# DirSpd.net
KiCad netlist of a schematic drawn in EAGLE
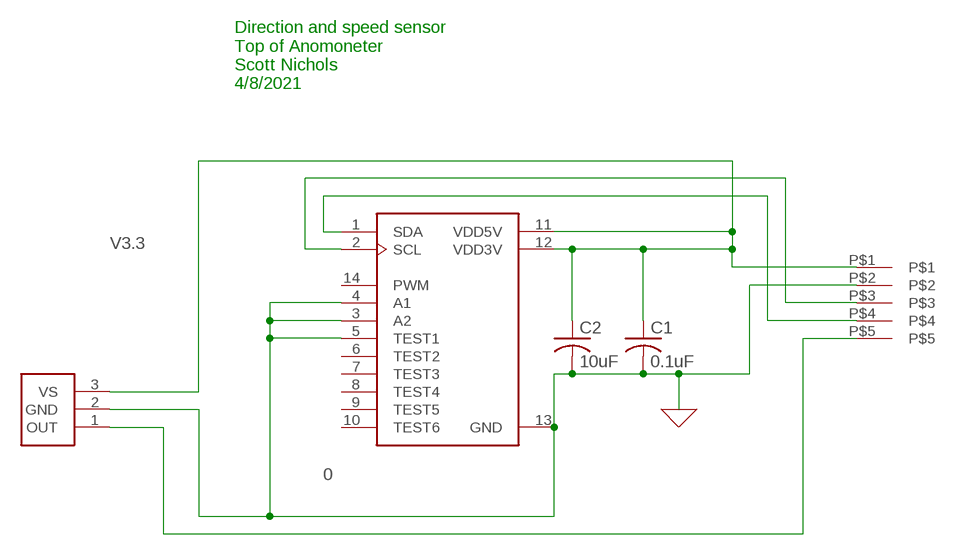
[diagram p0: schematic, sheet 1]

(export (version "E")
  (design (tool "Eeschema 10.0.6"))
  (components
    (comp (ref "C1")
      (value "0.1uF")
      (footprint "eagle-import:C0805K")
      (libsource (lib "eagle-import") (part "C-USC0805K"))
    )
    (comp (ref "C2")
      (value "10uF")
      (footprint "eagle-import:C0805K")
      (libsource (lib "eagle-import") (part "C-USC0805K"))
    )
    (comp (ref "J1")
      (value "B05B-PASK")
      (footprint "eagle-import:B05B-PASK")
      (libsource (lib "eagle-import") (part "B05B-PASK"))
    )
    (comp (ref "U1")
      (value "AS5048B")
      (footprint "eagle-import:TSSOP14")
      (libsource (lib "eagle-import") (part "AS5048B"))
    )
    (comp (ref "U2")
      (value "SS451A")
      (footprint "eagle-import:TO-92-3")
      (libsource (lib "eagle-import") (part "HONEYWELLSS451A"))
    )
  )
  (nets
    (net (code "1") (name "/V3.3") (class "Default")
      (node (ref "C1") (pin "1") (pinfunction "1_1") (pintype "passive"))
      (node (ref "C2") (pin "1") (pinfunction "1_1") (pintype "passive"))
      (node (ref "J1") (pin "P$1") (pinfunction "P$1_P$1") (pintype "bidirectional"))
      (node (ref "U1") (pin "11") (pinfunction "VDD5V_11") (pintype "bidirectional"))
      (node (ref "U1") (pin "12") (pinfunction "VDD3V_12") (pintype "bidirectional"))
      (node (ref "U2") (pin "3") (pinfunction "VS_3") (pintype "power_in"))
    )
    (net (code "2") (name "GND") (class "Default")
      (node (ref "C1") (pin "2") (pinfunction "2_2") (pintype "passive"))
      (node (ref "C2") (pin "2") (pinfunction "2_2") (pintype "passive"))
      (node (ref "J1") (pin "P$2") (pinfunction "P$2_P$2") (pintype "bidirectional"))
      (node (ref "U1") (pin "13") (pinfunction "GND_13") (pintype "bidirectional"))
      (node (ref "U1") (pin "3") (pinfunction "A2_3") (pintype "bidirectional"))
      (node (ref "U1") (pin "4") (pinfunction "A1_4") (pintype "bidirectional"))
      (node (ref "U1") (pin "5") (pinfunction "TEST1_5") (pintype "bidirectional"))
      (node (ref "U2") (pin "2") (pinfunction "GND_2") (pintype "bidirectional"))
    )
    (net (code "3") (name "Net-(U1-SCL)") (class "Default")
      (node (ref "J1") (pin "P$3") (pinfunction "P$3_P$3") (pintype "bidirectional"))
      (node (ref "U1") (pin "2") (pinfunction "SCL_2") (pintype "bidirectional"))
    )
    (net (code "4") (name "Net-(U1-SDA)") (class "Default")
      (node (ref "J1") (pin "P$4") (pinfunction "P$4_P$4") (pintype "bidirectional"))
      (node (ref "U1") (pin "1") (pinfunction "SDA_1") (pintype "bidirectional"))
    )
    (net (code "5") (name "Net-(U2-OUT)") (class "Default")
      (node (ref "J1") (pin "P$5") (pinfunction "P$5_P$5") (pintype "bidirectional"))
      (node (ref "U2") (pin "1") (pinfunction "OUT_1") (pintype "output"))
    )
    (net (code "6") (name "unconnected-(U1-PWM-Pad14)") (class "Default")
      (node (ref "U1") (pin "14") (pinfunction "PWM_14") (pintype "bidirectional"))
    )
    (net (code "7") (name "unconnected-(U1-TEST2-Pad6)") (class "Default")
      (node (ref "U1") (pin "6") (pinfunction "TEST2_6") (pintype "bidirectional"))
    )
    (net (code "8") (name "unconnected-(U1-TEST3-Pad7)") (class "Default")
      (node (ref "U1") (pin "7") (pinfunction "TEST3_7") (pintype "bidirectional"))
    )
    (net (code "9") (name "unconnected-(U1-TEST4-Pad8)") (class "Default")
      (node (ref "U1") (pin "8") (pinfunction "TEST4_8") (pintype "bidirectional"))
    )
    (net (code "10") (name "unconnected-(U1-TEST5-Pad9)") (class "Default")
      (node (ref "U1") (pin "9") (pinfunction "TEST5_9") (pintype "bidirectional"))
    )
    (net (code "11") (name "unconnected-(U1-TEST6-Pad10)") (class "Default")
      (node (ref "U1") (pin "10") (pinfunction "TEST6_10") (pintype "bidirectional"))
    )
  )
)
